# Peripheral.net
KiCad netlist of a schematic drawn in Altium Designer
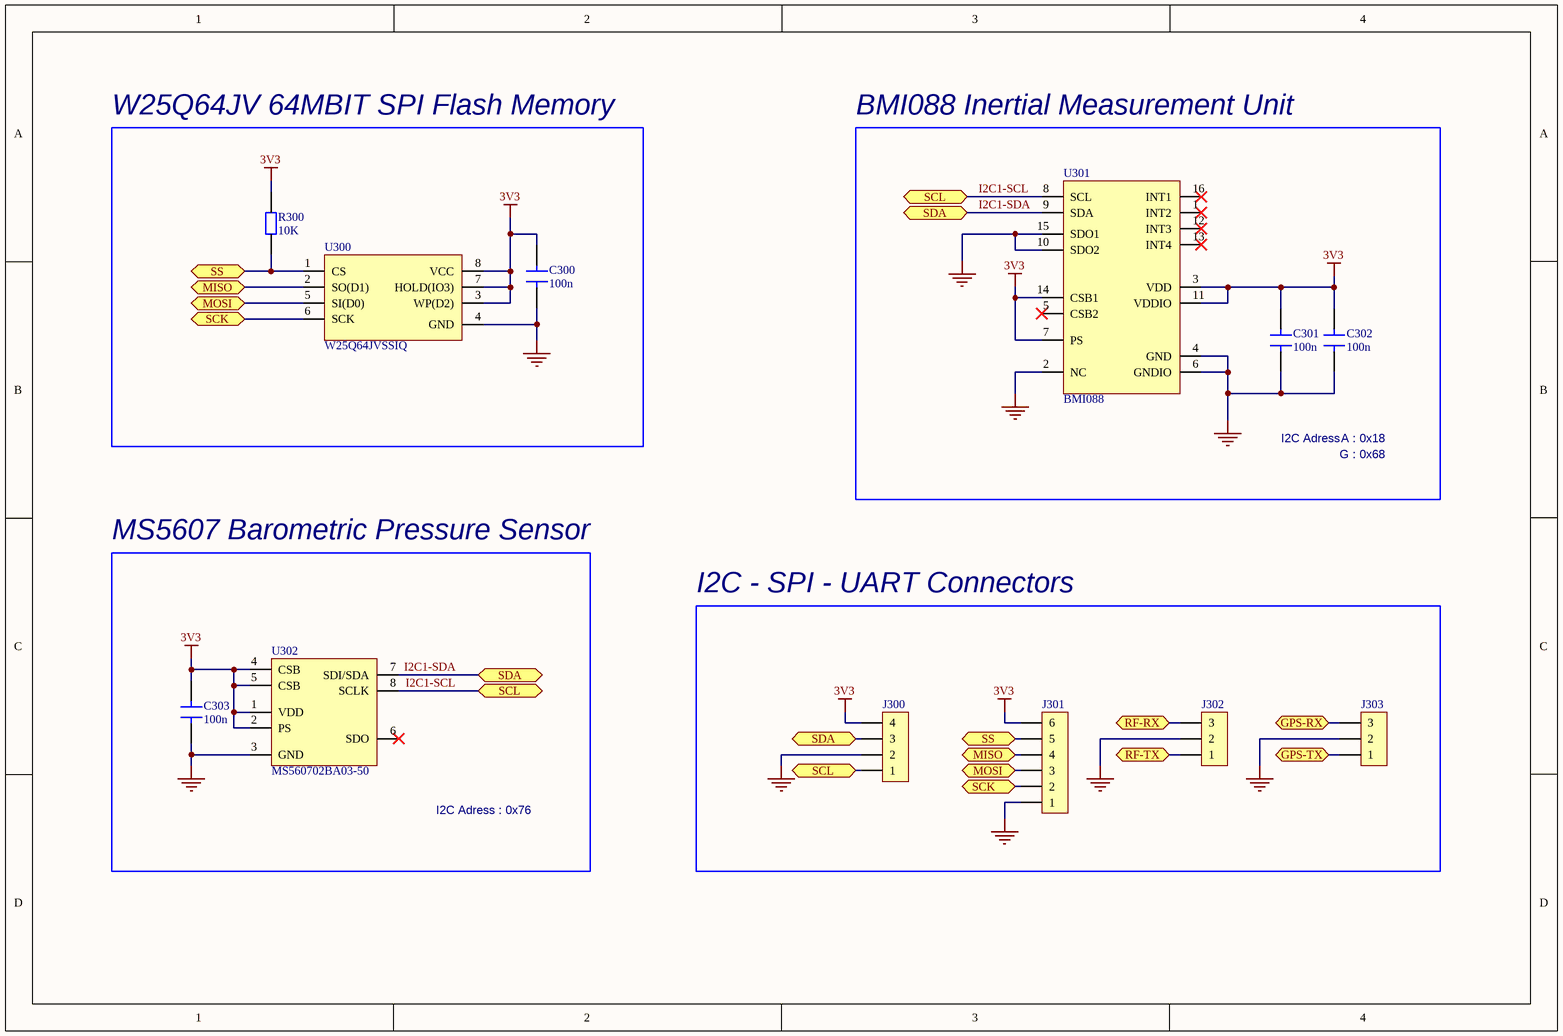
[diagram p0: Peripheral.SchDoc]

(export (version "E")
  (design (tool "Eeschema 10.0.6"))
  (components
    (comp (ref "C300")
      (value "100n")
      (footprint "CAP 0603")
      (description "Capacitor SMD 0603 50V")
      (libsource (lib "Schlib") (part "CAP 0603 50V"))
    )
    (comp (ref "C301")
      (value "100n")
      (footprint "CAP 0603")
      (description "Capacitor SMD 0603 50V")
      (libsource (lib "Schlib") (part "CAP 0603 50V"))
    )
    (comp (ref "C302")
      (value "100n")
      (footprint "CAP 0603")
      (description "Capacitor SMD 0603 50V")
      (libsource (lib "Schlib") (part "CAP 0603 50V"))
    )
    (comp (ref "C303")
      (value "100n")
      (footprint "CAP 0603")
      (description "Capacitor SMD 0603 50V")
      (libsource (lib "Schlib") (part "CAP 0603 50V"))
    )
    (comp (ref "J300")
      (value "1x4 HEADER MALE")
      (footprint "1X4 HEADER MALE")
      (libsource (lib "Schlib") (part "1x4 HEADER MALE"))
    )
    (comp (ref "J301")
      (value "1x6 HEADER MALE")
      (footprint "1X6 HEADER MALE")
      (libsource (lib "Schlib") (part "1x6 HEADER MALE"))
    )
    (comp (ref "J302")
      (value "JST B3B-XH-A")
      (footprint "JST_B3B-XH-A")
      (description "Connector Header, XH Series, 3 Position, 2.50mm, Through Hole, Press-Fit, Solder, Natural")
      (fields
        (field (name "MANUFACTURER") "JST")
        (field (name "MANUFACTURER PART NUMBER") "B3B-XH-A(LF)(SN)")
      )
      (libsource (lib "Schlib") (part "JST B3B-XH-A"))
    )
    (comp (ref "J303")
      (value "JST B3B-XH-A")
      (footprint "JST_B3B-XH-A")
      (description "Connector Header, XH Series, 3 Position, 2.50mm, Through Hole, Press-Fit, Solder, Natural")
      (fields
        (field (name "MANUFACTURER") "JST")
        (field (name "MANUFACTURER PART NUMBER") "B3B-XH-A(LF)(SN)")
      )
      (libsource (lib "Schlib") (part "JST B3B-XH-A"))
    )
    (comp (ref "R300")
      (value "10K")
      (footprint "RES 0603")
      (description "Resistor SMD 0603")
      (libsource (lib "Schlib") (part "RES 0603"))
    )
    (comp (ref "U300")
      (value "W25Q64JVSSIQ")
      (footprint "W25Q64JVSSIQ")
      (description "IC FLASH 64MBIT 104MHZ 8SOIC")
      (fields (field (name "MANUFACTURER") "Winbond"))
      (libsource (lib "Schlib") (part "W25Q64JVSSIQ"))
    )
    (comp (ref "U301")
      (value "BMI088")
      (footprint "BMI088")
      (description "BMI088 Series 3.6 V 6 Axis Digital Output Accelerometer Motion Sensor - LGA-16")
      (fields (field (name "MANUFACTURER") "Bosch Tools"))
      (libsource (lib "Schlib") (part "BMI088"))
    )
    (comp (ref "U302")
      (value "MS560702BA03-50")
      (footprint "MS5607-02BA3")
      (description "Board Mount Pressure Sensor 0.01bar to 1.2bar Absolute 8-Pin QFN T/R")
      (fields (field (name "MANUFACTURER") "Measurement Specialties"))
      (libsource (lib "Schlib") (part "MS560702BA03-50"))
    )
  )
  (nets
    (net (code "1") (name "/GPS-RX") (class "Default")
      (node (ref "J303") (pin "3") (pinfunction "3_3") (pintype "passive"))
    )
    (net (code "2") (name "/GPS-TX") (class "Default")
      (node (ref "J303") (pin "1") (pinfunction "1_1") (pintype "passive"))
    )
    (net (code "3") (name "/I2C1-SCL") (class "Default")
      (node (ref "J300") (pin "1") (pinfunction "1_1") (pintype "passive"))
      (node (ref "U301") (pin "8") (pinfunction "SCL_8") (pintype "passive"))
      (node (ref "U302") (pin "8") (pinfunction "SCLK_8") (pintype "passive"))
    )
    (net (code "4") (name "/I2C1-SDA") (class "Default")
      (node (ref "J300") (pin "3") (pinfunction "3_3") (pintype "passive"))
      (node (ref "U301") (pin "9") (pinfunction "SDA_9") (pintype "passive"))
      (node (ref "U302") (pin "7") (pinfunction "SDI/SDA_7") (pintype "passive"))
    )
    (net (code "5") (name "/MISO") (class "Default")
      (node (ref "J301") (pin "4") (pinfunction "4_4") (pintype "passive"))
      (node (ref "U300") (pin "2") (pinfunction "SO(D1)_2") (pintype "passive"))
    )
    (net (code "6") (name "/MOSI") (class "Default")
      (node (ref "J301") (pin "3") (pinfunction "3_3") (pintype "passive"))
      (node (ref "U300") (pin "5") (pinfunction "SI(D0)_5") (pintype "passive"))
    )
    (net (code "7") (name "/RF-RX") (class "Default")
      (node (ref "J302") (pin "3") (pinfunction "3_3") (pintype "passive"))
    )
    (net (code "8") (name "/RF-TX") (class "Default")
      (node (ref "J302") (pin "1") (pinfunction "1_1") (pintype "passive"))
    )
    (net (code "9") (name "/SCK") (class "Default")
      (node (ref "J301") (pin "2") (pinfunction "2_2") (pintype "passive"))
      (node (ref "U300") (pin "6") (pinfunction "SCK_6") (pintype "passive"))
    )
    (net (code "10") (name "/SS") (class "Default")
      (node (ref "J301") (pin "5") (pinfunction "5_5") (pintype "passive"))
      (node (ref "R300") (pin "1") (pinfunction "1_1") (pintype "passive"))
      (node (ref "U300") (pin "1") (pinfunction "CS_1") (pintype "passive"))
    )
    (net (code "11") (name "3V3") (class "Default")
      (node (ref "C300") (pin "1") (pinfunction "1_1") (pintype "passive"))
      (node (ref "C301") (pin "2") (pinfunction "2_2") (pintype "passive"))
      (node (ref "C302") (pin "2") (pinfunction "2_2") (pintype "passive"))
      (node (ref "C303") (pin "2") (pinfunction "2_2") (pintype "passive"))
      (node (ref "J300") (pin "4") (pinfunction "4_4") (pintype "passive"))
      (node (ref "J301") (pin "6") (pinfunction "6_6") (pintype "passive"))
      (node (ref "R300") (pin "2") (pinfunction "2_2") (pintype "passive"))
      (node (ref "U300") (pin "3") (pinfunction "WP(D2)_3") (pintype "passive"))
      (node (ref "U300") (pin "7") (pinfunction "HOLD(IO3)_7") (pintype "passive"))
      (node (ref "U300") (pin "8") (pinfunction "VCC_8") (pintype "passive"))
      (node (ref "U301") (pin "11") (pinfunction "VDDIO_11") (pintype "passive"))
      (node (ref "U301") (pin "14") (pinfunction "CSB1_14") (pintype "passive"))
      (node (ref "U301") (pin "3") (pinfunction "VDD_3") (pintype "passive"))
      (node (ref "U301") (pin "7") (pinfunction "PS_7") (pintype "passive"))
      (node (ref "U302") (pin "1") (pinfunction "VDD_1") (pintype "passive"))
      (node (ref "U302") (pin "2") (pinfunction "PS_2") (pintype "passive"))
      (node (ref "U302") (pin "4") (pinfunction "CSB_4") (pintype "passive"))
      (node (ref "U302") (pin "5") (pinfunction "CSB_5") (pintype "passive"))
    )
    (net (code "12") (name "GND") (class "Default")
      (node (ref "C300") (pin "2") (pinfunction "2_2") (pintype "passive"))
      (node (ref "C301") (pin "1") (pinfunction "1_1") (pintype "passive"))
      (node (ref "C302") (pin "1") (pinfunction "1_1") (pintype "passive"))
      (node (ref "C303") (pin "1") (pinfunction "1_1") (pintype "passive"))
      (node (ref "J300") (pin "2") (pinfunction "2_2") (pintype "passive"))
      (node (ref "J301") (pin "1") (pinfunction "1_1") (pintype "passive"))
      (node (ref "J302") (pin "2") (pinfunction "2_2") (pintype "passive"))
      (node (ref "J303") (pin "2") (pinfunction "2_2") (pintype "passive"))
      (node (ref "U300") (pin "4") (pinfunction "GND_4") (pintype "passive"))
      (node (ref "U301") (pin "10") (pinfunction "SDO2_10") (pintype "passive"))
      (node (ref "U301") (pin "15") (pinfunction "SDO1_15") (pintype "passive"))
      (node (ref "U301") (pin "2") (pinfunction "NC_2") (pintype "passive"))
      (node (ref "U301") (pin "4") (pinfunction "GND_4") (pintype "passive"))
      (node (ref "U301") (pin "6") (pinfunction "GNDIO_6") (pintype "passive"))
      (node (ref "U302") (pin "3") (pinfunction "GND_3") (pintype "passive"))
    )
    (net (code "13") (name "unconnected-(U301-CSB2-Pad5)") (class "Default")
      (node (ref "U301") (pin "5") (pinfunction "CSB2_5") (pintype "passive+no_connect"))
    )
    (net (code "14") (name "unconnected-(U301-INT1-Pad16)") (class "Default")
      (node (ref "U301") (pin "16") (pinfunction "INT1_16") (pintype "passive+no_connect"))
    )
    (net (code "15") (name "unconnected-(U301-INT2-Pad1)") (class "Default")
      (node (ref "U301") (pin "1") (pinfunction "INT2_1") (pintype "passive+no_connect"))
    )
    (net (code "16") (name "unconnected-(U301-INT3-Pad12)") (class "Default")
      (node (ref "U301") (pin "12") (pinfunction "INT3_12") (pintype "passive+no_connect"))
    )
    (net (code "17") (name "unconnected-(U301-INT4-Pad13)") (class "Default")
      (node (ref "U301") (pin "13") (pinfunction "INT4_13") (pintype "passive+no_connect"))
    )
    (net (code "18") (name "unconnected-(U302-SDO-Pad6)") (class "Default")
      (node (ref "U302") (pin "6") (pinfunction "SDO_6") (pintype "passive+no_connect"))
    )
  )
)
